# SCH_esp32.net
KiCad netlist of a schematic drawn in Altium Designer
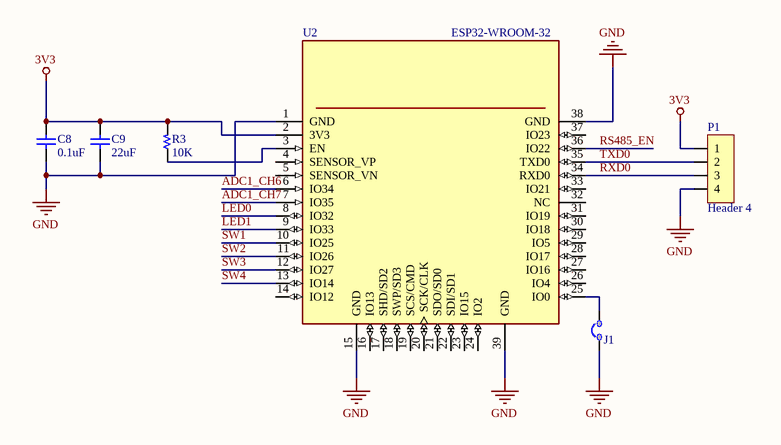
[diagram p0: SCH_esp32.SchDoc]

(export (version "E")
  (design (tool "Eeschema 10.0.6"))
  (components
    (comp (ref "C8")
      (value "0.1uF")
      (footprint "C 0805")
      (description "Capacitor non-pol")
      (libsource (lib "chipfc_libs") (part "Capacitor NP"))
    )
    (comp (ref "C9")
      (value "22uF")
      (footprint "C 0805")
      (description "Capacitor non-pol")
      (libsource (lib "chipfc_libs") (part "Capacitor NP"))
    )
    (comp (ref "J1")
      (value "JUMP 2")
      (footprint "JUMP/2/Close")
      (libsource (lib "chipfc_libs") (part "JUMP 2"))
    )
    (comp (ref "P1")
      (value "Header 4")
      (footprint "HDR/Header/4")
      (description "Header, 4-Pin")
      (libsource (lib "connectors") (part "Header 4"))
    )
    (comp (ref "R3")
      (value "10K")
      (footprint "R 0805")
      (description "Resistor")
      (libsource (lib "chipfc_libs") (part "Resistor"))
    )
    (comp (ref "U2")
      (value "ESP32-WROOM-32")
      (footprint "MODULE_ESP32-WROOM-32")
      (fields (field (name "MF") "Espressif Systems") (field (name "MP") "ESP32-WROOM-32D"))
      (libsource (lib "ESP32") (part "ESP32-WROOM-32"))
    )
  )
  (nets
    (net (code "1") (name "/ADC1_CH6") (class "Default")
      (node (ref "U2") (pin "6") (pinfunction "IO34_6") (pintype "input"))
    )
    (net (code "2") (name "/ADC1_CH7") (class "Default")
      (node (ref "U2") (pin "7") (pinfunction "IO35_7") (pintype "input"))
    )
    (net (code "3") (name "/LED0") (class "Default")
      (node (ref "U2") (pin "8") (pinfunction "IO32_8") (pintype "bidirectional"))
    )
    (net (code "4") (name "/LED1") (class "Default")
      (node (ref "U2") (pin "9") (pinfunction "IO33_9") (pintype "bidirectional"))
    )
    (net (code "5") (name "/RS485_EN") (class "Default")
      (node (ref "U2") (pin "36") (pinfunction "IO22_36") (pintype "bidirectional"))
    )
    (net (code "6") (name "/RXD0") (class "Default")
      (node (ref "P1") (pin "3") (pinfunction "3_3") (pintype "passive"))
      (node (ref "U2") (pin "34") (pinfunction "RXD0_34") (pintype "bidirectional"))
    )
    (net (code "7") (name "/SW1") (class "Default")
      (node (ref "U2") (pin "10") (pinfunction "IO25_10") (pintype "bidirectional"))
    )
    (net (code "8") (name "/SW2") (class "Default")
      (node (ref "U2") (pin "11") (pinfunction "IO26_11") (pintype "bidirectional"))
    )
    (net (code "9") (name "/SW3") (class "Default")
      (node (ref "U2") (pin "12") (pinfunction "IO27_12") (pintype "bidirectional"))
    )
    (net (code "10") (name "/SW4") (class "Default")
      (node (ref "U2") (pin "13") (pinfunction "IO14_13") (pintype "bidirectional"))
    )
    (net (code "11") (name "/TXD0") (class "Default")
      (node (ref "P1") (pin "2") (pinfunction "2_2") (pintype "passive"))
      (node (ref "U2") (pin "35") (pinfunction "TXD0_35") (pintype "bidirectional"))
    )
    (net (code "12") (name "3V3") (class "Default")
      (node (ref "C8") (pin "1") (pinfunction "1_1") (pintype "passive"))
      (node (ref "C9") (pin "1") (pinfunction "1_1") (pintype "passive"))
      (node (ref "P1") (pin "1") (pinfunction "1_1") (pintype "passive"))
      (node (ref "R3") (pin "2") (pinfunction "2_2") (pintype "passive"))
      (node (ref "U2") (pin "2") (pinfunction "3V3_2") (pintype "power_in"))
    )
    (net (code "13") (name "GND") (class "Default")
      (node (ref "C8") (pin "2") (pinfunction "2_2") (pintype "passive"))
      (node (ref "C9") (pin "2") (pinfunction "2_2") (pintype "passive"))
      (node (ref "J1") (pin "1") (pinfunction "1_1") (pintype "passive"))
      (node (ref "P1") (pin "4") (pinfunction "4_4") (pintype "passive"))
      (node (ref "U2") (pin "1") (pinfunction "GND_1") (pintype "power_in"))
      (node (ref "U2") (pin "15") (pinfunction "GND_15") (pintype "power_in"))
      (node (ref "U2") (pin "38") (pinfunction "GND_38") (pintype "power_in"))
      (node (ref "U2") (pin "39") (pinfunction "GND_39") (pintype "power_in"))
    )
    (net (code "14") (name "Net-(U2-EN)") (class "Default")
      (node (ref "R3") (pin "1") (pinfunction "1_1") (pintype "passive"))
      (node (ref "U2") (pin "3") (pinfunction "EN_3") (pintype "input"))
    )
    (net (code "15") (name "Net-(U2-IO0)") (class "Default")
      (node (ref "J1") (pin "2") (pinfunction "2_2") (pintype "passive"))
      (node (ref "U2") (pin "25") (pinfunction "IO0_25") (pintype "bidirectional"))
    )
    (net (code "16") (name "unconnected-(U2-IO2-Pad24)") (class "Default")
      (node (ref "U2") (pin "24") (pinfunction "IO2_24") (pintype "bidirectional"))
    )
    (net (code "17") (name "unconnected-(U2-IO4-Pad26)") (class "Default")
      (node (ref "U2") (pin "26") (pinfunction "IO4_26") (pintype "bidirectional"))
    )
    (net (code "18") (name "unconnected-(U2-IO5-Pad29)") (class "Default")
      (node (ref "U2") (pin "29") (pinfunction "IO5_29") (pintype "bidirectional"))
    )
    (net (code "19") (name "unconnected-(U2-IO12-Pad14)") (class "Default")
      (node (ref "U2") (pin "14") (pinfunction "IO12_14") (pintype "bidirectional"))
    )
    (net (code "20") (name "unconnected-(U2-IO13-Pad16)") (class "Default")
      (node (ref "U2") (pin "16") (pinfunction "IO13_16") (pintype "bidirectional"))
    )
    (net (code "21") (name "unconnected-(U2-IO15-Pad23)") (class "Default")
      (node (ref "U2") (pin "23") (pinfunction "IO15_23") (pintype "bidirectional"))
    )
    (net (code "22") (name "unconnected-(U2-IO16-Pad27)") (class "Default")
      (node (ref "U2") (pin "27") (pinfunction "IO16_27") (pintype "bidirectional"))
    )
    (net (code "23") (name "unconnected-(U2-IO17-Pad28)") (class "Default")
      (node (ref "U2") (pin "28") (pinfunction "IO17_28") (pintype "bidirectional"))
    )
    (net (code "24") (name "unconnected-(U2-IO18-Pad30)") (class "Default")
      (node (ref "U2") (pin "30") (pinfunction "IO18_30") (pintype "bidirectional"))
    )
    (net (code "25") (name "unconnected-(U2-IO19-Pad31)") (class "Default")
      (node (ref "U2") (pin "31") (pinfunction "IO19_31") (pintype "bidirectional"))
    )
    (net (code "26") (name "unconnected-(U2-IO21-Pad33)") (class "Default")
      (node (ref "U2") (pin "33") (pinfunction "IO21_33") (pintype "bidirectional"))
    )
    (net (code "27") (name "unconnected-(U2-IO23-Pad37)") (class "Default")
      (node (ref "U2") (pin "37") (pinfunction "IO23_37") (pintype "bidirectional"))
    )
    (net (code "28") (name "unconnected-(U2-NC-Pad32)") (class "Default")
      (node (ref "U2") (pin "32") (pinfunction "NC_32") (pintype "power_in"))
    )
    (net (code "29") (name "unconnected-(U2-SCK{slash}CLK-Pad20)") (class "Default")
      (node (ref "U2") (pin "20") (pinfunction "SCK/CLK_20") (pintype "bidirectional"))
    )
    (net (code "30") (name "unconnected-(U2-SCS{slash}CMD-Pad19)") (class "Default")
      (node (ref "U2") (pin "19") (pinfunction "SCS/CMD_19") (pintype "bidirectional"))
    )
    (net (code "31") (name "unconnected-(U2-SDI{slash}SD1-Pad22)") (class "Default")
      (node (ref "U2") (pin "22") (pinfunction "SDI/SD1_22") (pintype "bidirectional"))
    )
    (net (code "32") (name "unconnected-(U2-SDO{slash}SD0-Pad21)") (class "Default")
      (node (ref "U2") (pin "21") (pinfunction "SDO/SD0_21") (pintype "bidirectional"))
    )
    (net (code "33") (name "unconnected-(U2-SENSOR_VN-Pad5)") (class "Default")
      (node (ref "U2") (pin "5") (pinfunction "SENSOR_VN_5") (pintype "input"))
    )
    (net (code "34") (name "unconnected-(U2-SENSOR_VP-Pad4)") (class "Default")
      (node (ref "U2") (pin "4") (pinfunction "SENSOR_VP_4") (pintype "input"))
    )
    (net (code "35") (name "unconnected-(U2-SHD{slash}SD2-Pad17)") (class "Default")
      (node (ref "U2") (pin "17") (pinfunction "SHD/SD2_17") (pintype "bidirectional"))
    )
    (net (code "36") (name "unconnected-(U2-SWP{slash}SD3-Pad18)") (class "Default")
      (node (ref "U2") (pin "18") (pinfunction "SWP/SD3_18") (pintype "bidirectional"))
    )
  )
)
